# components.net
KiCad netlist of a schematic drawn in EAGLE
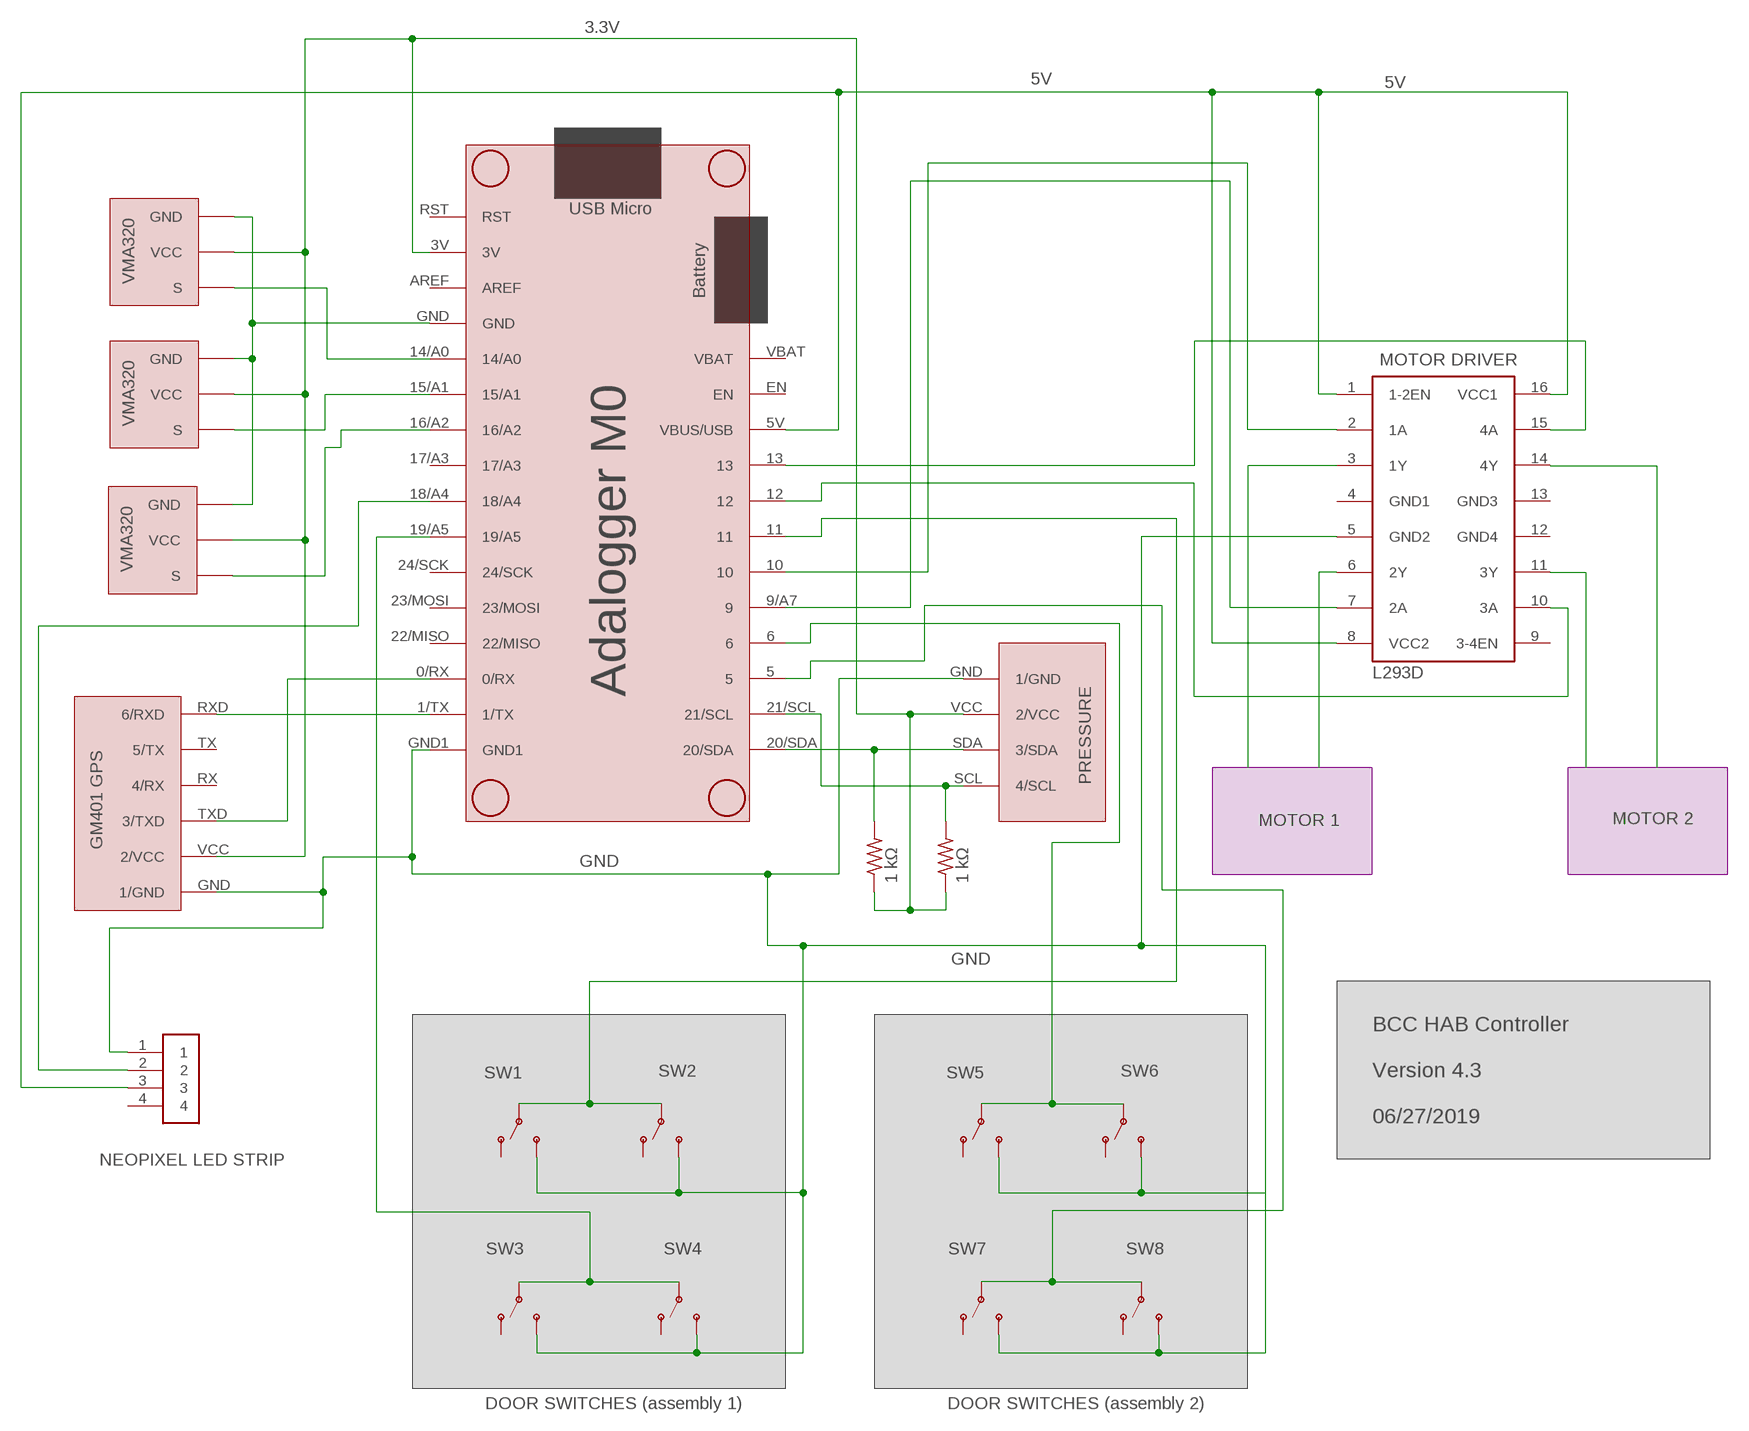
[diagram p0: schematic, sheet 1]

(export (version "E")
  (design (tool "Eeschema 10.0.6"))
  (components
    (comp (ref "CN1")
      (value "1X4SMT")
      (footprint "eagle-import:1X4-SMT")
      (libsource (lib "eagle-import") (part "1X4SMT"))
    )
    (comp (ref "IC1")
      (value "L293D")
      (footprint "eagle-import:DIL16")
      (libsource (lib "eagle-import") (part "L293D"))
    )
    (comp (ref "PRESSURE_1")
      (value "PRESSURE")
      (footprint "eagle-import:HSC_PRESSURE")
      (libsource (lib "eagle-import") (part "PRESSURE"))
    )
    (comp (ref "R6")
      (value "1 kΩ")
      (footprint "eagle-import:0204_7")
      (libsource (lib "eagle-import") (part "R-US_0204/7"))
    )
    (comp (ref "R7")
      (value "1 kΩ")
      (footprint "eagle-import:0204_7")
      (libsource (lib "eagle-import") (part "R-US_0204/7"))
    )
    (comp (ref "SW1")
      (value "SWITCH-SPDT-PTH-11.6X4.0MM")
      (footprint "eagle-import:SWITCH_SPDT_PTH_11.6X4.0MM")
      (libsource (lib "eagle-import") (part "SWITCH-SPDT-PTH-11.6X4.0MM"))
    )
    (comp (ref "SW2")
      (value "SWITCH-SPDT-PTH-11.6X4.0MM")
      (footprint "eagle-import:SWITCH_SPDT_PTH_11.6X4.0MM")
      (libsource (lib "eagle-import") (part "SWITCH-SPDT-PTH-11.6X4.0MM"))
    )
    (comp (ref "SW3")
      (value "SWITCH-SPDT-PTH-11.6X4.0MM")
      (footprint "eagle-import:SWITCH_SPDT_PTH_11.6X4.0MM")
      (libsource (lib "eagle-import") (part "SWITCH-SPDT-PTH-11.6X4.0MM"))
    )
    (comp (ref "SW4")
      (value "SWITCH-SPDT-PTH-11.6X4.0MM")
      (footprint "eagle-import:SWITCH_SPDT_PTH_11.6X4.0MM")
      (libsource (lib "eagle-import") (part "SWITCH-SPDT-PTH-11.6X4.0MM"))
    )
    (comp (ref "SW5")
      (value "SWITCH-SPDT-PTH-11.6X4.0MM")
      (footprint "eagle-import:SWITCH_SPDT_PTH_11.6X4.0MM")
      (libsource (lib "eagle-import") (part "SWITCH-SPDT-PTH-11.6X4.0MM"))
    )
    (comp (ref "SW6")
      (value "SWITCH-SPDT-PTH-11.6X4.0MM")
      (footprint "eagle-import:SWITCH_SPDT_PTH_11.6X4.0MM")
      (libsource (lib "eagle-import") (part "SWITCH-SPDT-PTH-11.6X4.0MM"))
    )
    (comp (ref "SW7")
      (value "SWITCH-SPDT-PTH-11.6X4.0MM")
      (footprint "eagle-import:SWITCH_SPDT_PTH_11.6X4.0MM")
      (libsource (lib "eagle-import") (part "SWITCH-SPDT-PTH-11.6X4.0MM"))
    )
    (comp (ref "SW8")
      (value "SWITCH-SPDT-PTH-11.6X4.0MM")
      (footprint "eagle-import:SWITCH_SPDT_PTH_11.6X4.0MM")
      (libsource (lib "eagle-import") (part "SWITCH-SPDT-PTH-11.6X4.0MM"))
    )
    (comp (ref "TEMP_1")
      (value "VMA320")
      (footprint "eagle-import:VMA320")
      (libsource (lib "eagle-import") (part "VMA320"))
    )
    (comp (ref "TEMP_2")
      (value "VMA320")
      (footprint "eagle-import:VMA320")
      (libsource (lib "eagle-import") (part "VMA320"))
    )
    (comp (ref "TEMP_3")
      (value "VMA320")
      (footprint "eagle-import:VMA320")
      (libsource (lib "eagle-import") (part "VMA320"))
    )
    (comp (ref "U$1")
      (value "ADALOGGER_M0")
      (footprint "eagle-import:BOARD")
      (libsource (lib "eagle-import") (part "ADALOGGER_M0"))
    )
    (comp (ref "U$3")
      (value "GPS")
      (footprint "eagle-import:GPS_BREAKOUT")
      (libsource (lib "eagle-import") (part "GPS"))
    )
  )
  (nets
    (net (code "1") (name "/3.3V") (class "Default")
      (node (ref "PRESSURE_1") (pin "VCC") (pinfunction "2/VCC_VCC") (pintype "bidirectional"))
      (node (ref "R6") (pin "1") (pinfunction "1_1") (pintype "passive"))
      (node (ref "R7") (pin "1") (pinfunction "1_1") (pintype "passive"))
      (node (ref "TEMP_1") (pin "VCC") (pinfunction "VCC_VCC") (pintype "bidirectional"))
      (node (ref "TEMP_2") (pin "VCC") (pinfunction "VCC_VCC") (pintype "bidirectional"))
      (node (ref "TEMP_3") (pin "VCC") (pinfunction "VCC_VCC") (pintype "bidirectional"))
      (node (ref "U$1") (pin "3V") (pinfunction "3V_3V") (pintype "bidirectional"))
      (node (ref "U$3") (pin "VCC") (pinfunction "2/VCC_VCC") (pintype "bidirectional"))
    )
    (net (code "2") (name "/5V") (class "Default")
      (node (ref "CN1") (pin "3") (pinfunction "3_3") (pintype "bidirectional"))
      (node (ref "IC1") (pin "1") (pinfunction "1-2EN_1") (pintype "input"))
      (node (ref "IC1") (pin "16") (pinfunction "VCC1_16") (pintype "power_in"))
      (node (ref "IC1") (pin "8") (pinfunction "VCC2_8") (pintype "power_in"))
      (node (ref "U$1") (pin "5V") (pinfunction "VBUS/USB_5V") (pintype "bidirectional"))
    )
    (net (code "3") (name "/GND") (class "Default")
      (node (ref "CN1") (pin "1") (pinfunction "1_1") (pintype "bidirectional"))
      (node (ref "IC1") (pin "5") (pinfunction "GND2_5") (pintype "power_in"))
      (node (ref "PRESSURE_1") (pin "GND") (pinfunction "1/GND_GND") (pintype "bidirectional"))
      (node (ref "SW1") (pin "3") (pinfunction "S_3") (pintype "passive"))
      (node (ref "SW2") (pin "3") (pinfunction "S_3") (pintype "passive"))
      (node (ref "SW3") (pin "3") (pinfunction "S_3") (pintype "passive"))
      (node (ref "SW4") (pin "3") (pinfunction "S_3") (pintype "passive"))
      (node (ref "SW5") (pin "3") (pinfunction "S_3") (pintype "passive"))
      (node (ref "SW6") (pin "3") (pinfunction "S_3") (pintype "passive"))
      (node (ref "SW7") (pin "3") (pinfunction "S_3") (pintype "passive"))
      (node (ref "SW8") (pin "3") (pinfunction "S_3") (pintype "passive"))
      (node (ref "U$1") (pin "GND1") (pinfunction "GND1_GND1") (pintype "bidirectional"))
      (node (ref "U$3") (pin "GND") (pinfunction "1/GND_GND") (pintype "bidirectional"))
    )
    (net (code "4") (name "/GND1") (class "Default")
      (node (ref "IC1") (pin "4") (pinfunction "GND1_4") (pintype "power_in"))
    )
    (net (code "5") (name "/GND3") (class "Default")
      (node (ref "IC1") (pin "13") (pinfunction "GND3_13") (pintype "power_in"))
    )
    (net (code "6") (name "/GND4") (class "Default")
      (node (ref "IC1") (pin "12") (pinfunction "GND4_12") (pintype "power_in"))
    )
    (net (code "7") (name "Net-(CN1-Pad2)") (class "Default")
      (node (ref "CN1") (pin "2") (pinfunction "2_2") (pintype "bidirectional"))
      (node (ref "U$1") (pin "18/A4") (pinfunction "18/A4_18/A4") (pintype "bidirectional"))
    )
    (net (code "8") (name "Net-(IC1-1A)") (class "Default")
      (node (ref "IC1") (pin "2") (pinfunction "1A_2") (pintype "input"))
      (node (ref "U$1") (pin "10") (pinfunction "10_10") (pintype "bidirectional"))
    )
    (net (code "9") (name "Net-(IC1-2A)") (class "Default")
      (node (ref "IC1") (pin "7") (pinfunction "2A_7") (pintype "input"))
      (node (ref "U$1") (pin "9/A7") (pinfunction "9_9/A7") (pintype "bidirectional"))
    )
    (net (code "10") (name "Net-(IC1-3A)") (class "Default")
      (node (ref "IC1") (pin "10") (pinfunction "3A_10") (pintype "input"))
      (node (ref "U$1") (pin "12") (pinfunction "12_12") (pintype "bidirectional"))
    )
    (net (code "11") (name "Net-(IC1-4A)") (class "Default")
      (node (ref "IC1") (pin "15") (pinfunction "4A_15") (pintype "input"))
      (node (ref "U$1") (pin "13") (pinfunction "13_13") (pintype "bidirectional"))
    )
    (net (code "12") (name "Net-(PRESSURE_1-3{slash}SDA)") (class "Default")
      (node (ref "PRESSURE_1") (pin "SDA") (pinfunction "3/SDA_SDA") (pintype "bidirectional"))
      (node (ref "R6") (pin "2") (pinfunction "2_2") (pintype "passive"))
      (node (ref "U$1") (pin "20/SDA") (pinfunction "20/SDA_20/SDA") (pintype "bidirectional"))
    )
    (net (code "13") (name "Net-(PRESSURE_1-4{slash}SCL)") (class "Default")
      (node (ref "PRESSURE_1") (pin "SCL") (pinfunction "4/SCL_SCL") (pintype "bidirectional"))
      (node (ref "R7") (pin "2") (pinfunction "2_2") (pintype "passive"))
      (node (ref "U$1") (pin "21/SCL") (pinfunction "21/SCL_21/SCL") (pintype "bidirectional"))
    )
    (net (code "14") (name "Net-(SW1-P)") (class "Default")
      (node (ref "SW1") (pin "2") (pinfunction "P_2") (pintype "passive"))
      (node (ref "SW2") (pin "2") (pinfunction "P_2") (pintype "passive"))
      (node (ref "U$1") (pin "11") (pinfunction "11_11") (pintype "bidirectional"))
    )
    (net (code "15") (name "Net-(SW3-P)") (class "Default")
      (node (ref "SW3") (pin "2") (pinfunction "P_2") (pintype "passive"))
      (node (ref "SW4") (pin "2") (pinfunction "P_2") (pintype "passive"))
      (node (ref "U$1") (pin "19/A5") (pinfunction "19/A5_19/A5") (pintype "bidirectional"))
    )
    (net (code "16") (name "Net-(SW5-P)") (class "Default")
      (node (ref "SW5") (pin "2") (pinfunction "P_2") (pintype "passive"))
      (node (ref "SW6") (pin "2") (pinfunction "P_2") (pintype "passive"))
      (node (ref "U$1") (pin "6") (pinfunction "6_6") (pintype "bidirectional"))
    )
    (net (code "17") (name "Net-(SW7-P)") (class "Default")
      (node (ref "SW7") (pin "2") (pinfunction "P_2") (pintype "passive"))
      (node (ref "SW8") (pin "2") (pinfunction "P_2") (pintype "passive"))
      (node (ref "U$1") (pin "5") (pinfunction "5_5") (pintype "bidirectional"))
    )
    (net (code "18") (name "Net-(TEMP_1-PadGND)") (class "Default")
      (node (ref "TEMP_1") (pin "GND") (pinfunction "GND_GND") (pintype "bidirectional"))
      (node (ref "TEMP_2") (pin "GND") (pinfunction "GND_GND") (pintype "bidirectional"))
      (node (ref "TEMP_3") (pin "GND") (pinfunction "GND_GND") (pintype "bidirectional"))
      (node (ref "U$1") (pin "GND") (pinfunction "GND_GND") (pintype "bidirectional"))
    )
    (net (code "19") (name "Net-(TEMP_1-PadS)") (class "Default")
      (node (ref "TEMP_1") (pin "S") (pinfunction "S_S") (pintype "bidirectional"))
      (node (ref "U$1") (pin "16/A2") (pinfunction "16/A2_16/A2") (pintype "bidirectional"))
    )
    (net (code "20") (name "Net-(TEMP_2-PadS)") (class "Default")
      (node (ref "TEMP_2") (pin "S") (pinfunction "S_S") (pintype "bidirectional"))
      (node (ref "U$1") (pin "14/A0") (pinfunction "14/A0_14/A0") (pintype "bidirectional"))
    )
    (net (code "21") (name "Net-(TEMP_3-PadS)") (class "Default")
      (node (ref "TEMP_3") (pin "S") (pinfunction "S_S") (pintype "bidirectional"))
      (node (ref "U$1") (pin "15/A1") (pinfunction "15/A1_15/A1") (pintype "bidirectional"))
    )
    (net (code "22") (name "Net-(U$3-3{slash}TXD)") (class "Default")
      (node (ref "U$1") (pin "0/RX") (pinfunction "0/RX_0/RX") (pintype "bidirectional"))
      (node (ref "U$3") (pin "TXD") (pinfunction "3/TXD_TXD") (pintype "bidirectional"))
    )
    (net (code "23") (name "Net-(U$3-6{slash}RXD)") (class "Default")
      (node (ref "U$1") (pin "1/TX") (pinfunction "1/TX_1/TX") (pintype "bidirectional"))
      (node (ref "U$3") (pin "RXD") (pinfunction "6/RXD_RXD") (pintype "bidirectional"))
    )
    (net (code "24") (name "unconnected-(CN1-Pad4)") (class "Default")
      (node (ref "CN1") (pin "4") (pinfunction "4_4") (pintype "bidirectional"))
    )
    (net (code "25") (name "unconnected-(IC1-1Y-Pad3)") (class "Default")
      (node (ref "IC1") (pin "3") (pinfunction "1Y_3") (pintype "output"))
    )
    (net (code "26") (name "unconnected-(IC1-2Y-Pad6)") (class "Default")
      (node (ref "IC1") (pin "6") (pinfunction "2Y_6") (pintype "output"))
    )
    (net (code "27") (name "unconnected-(IC1-3-4EN-Pad9)") (class "Default")
      (node (ref "IC1") (pin "9") (pinfunction "3-4EN_9") (pintype "input"))
    )
    (net (code "28") (name "unconnected-(IC1-3Y-Pad11)") (class "Default")
      (node (ref "IC1") (pin "11") (pinfunction "3Y_11") (pintype "output"))
    )
    (net (code "29") (name "unconnected-(IC1-4Y-Pad14)") (class "Default")
      (node (ref "IC1") (pin "14") (pinfunction "4Y_14") (pintype "output"))
    )
    (net (code "30") (name "unconnected-(SW1-O-Pad1)") (class "Default")
      (node (ref "SW1") (pin "1") (pinfunction "O_1") (pintype "passive"))
    )
    (net (code "31") (name "unconnected-(SW2-O-Pad1)") (class "Default")
      (node (ref "SW2") (pin "1") (pinfunction "O_1") (pintype "passive"))
    )
    (net (code "32") (name "unconnected-(SW3-O-Pad1)") (class "Default")
      (node (ref "SW3") (pin "1") (pinfunction "O_1") (pintype "passive"))
    )
    (net (code "33") (name "unconnected-(SW4-O-Pad1)") (class "Default")
      (node (ref "SW4") (pin "1") (pinfunction "O_1") (pintype "passive"))
    )
    (net (code "34") (name "unconnected-(SW5-O-Pad1)") (class "Default")
      (node (ref "SW5") (pin "1") (pinfunction "O_1") (pintype "passive"))
    )
    (net (code "35") (name "unconnected-(SW6-O-Pad1)") (class "Default")
      (node (ref "SW6") (pin "1") (pinfunction "O_1") (pintype "passive"))
    )
    (net (code "36") (name "unconnected-(SW7-O-Pad1)") (class "Default")
      (node (ref "SW7") (pin "1") (pinfunction "O_1") (pintype "passive"))
    )
    (net (code "37") (name "unconnected-(SW8-O-Pad1)") (class "Default")
      (node (ref "SW8") (pin "1") (pinfunction "O_1") (pintype "passive"))
    )
    (net (code "38") (name "unconnected-(U$1-Pad17{slash}A3)") (class "Default")
      (node (ref "U$1") (pin "17/A3") (pinfunction "17/A3_17/A3") (pintype "bidirectional"))
    )
    (net (code "39") (name "unconnected-(U$1-Pad22{slash}MISO)") (class "Default")
      (node (ref "U$1") (pin "22/MISO") (pinfunction "22/MISO_22/MISO") (pintype "bidirectional"))
    )
    (net (code "40") (name "unconnected-(U$1-Pad23{slash}MOSI)") (class "Default")
      (node (ref "U$1") (pin "23/MOSI") (pinfunction "23/MOSI_23/MOSI") (pintype "bidirectional"))
    )
    (net (code "41") (name "unconnected-(U$1-Pad24{slash}SCK)") (class "Default")
      (node (ref "U$1") (pin "24/SCK") (pinfunction "24/SCK_24/SCK") (pintype "bidirectional"))
    )
    (net (code "42") (name "unconnected-(U$1-PadAREF)") (class "Default")
      (node (ref "U$1") (pin "AREF") (pinfunction "AREF_AREF") (pintype "bidirectional"))
    )
    (net (code "43") (name "unconnected-(U$1-PadEN)") (class "Default")
      (node (ref "U$1") (pin "EN") (pinfunction "EN_EN") (pintype "bidirectional"))
    )
    (net (code "44") (name "unconnected-(U$1-PadRST)") (class "Default")
      (node (ref "U$1") (pin "RST") (pinfunction "RST_RST") (pintype "bidirectional"))
    )
    (net (code "45") (name "unconnected-(U$1-PadVBAT)") (class "Default")
      (node (ref "U$1") (pin "VBAT") (pinfunction "VBAT_VBAT") (pintype "bidirectional"))
    )
    (net (code "46") (name "unconnected-(U$3-4{slash}RX-PadRX)") (class "Default")
      (node (ref "U$3") (pin "RX") (pinfunction "4/RX_RX") (pintype "bidirectional"))
    )
    (net (code "47") (name "unconnected-(U$3-5{slash}TX-PadTX)") (class "Default")
      (node (ref "U$3") (pin "TX") (pinfunction "5/TX_TX") (pintype "bidirectional"))
    )
  )
)
